# lora-pi-hat.net
KiCad netlist of a schematic drawn in EAGLE
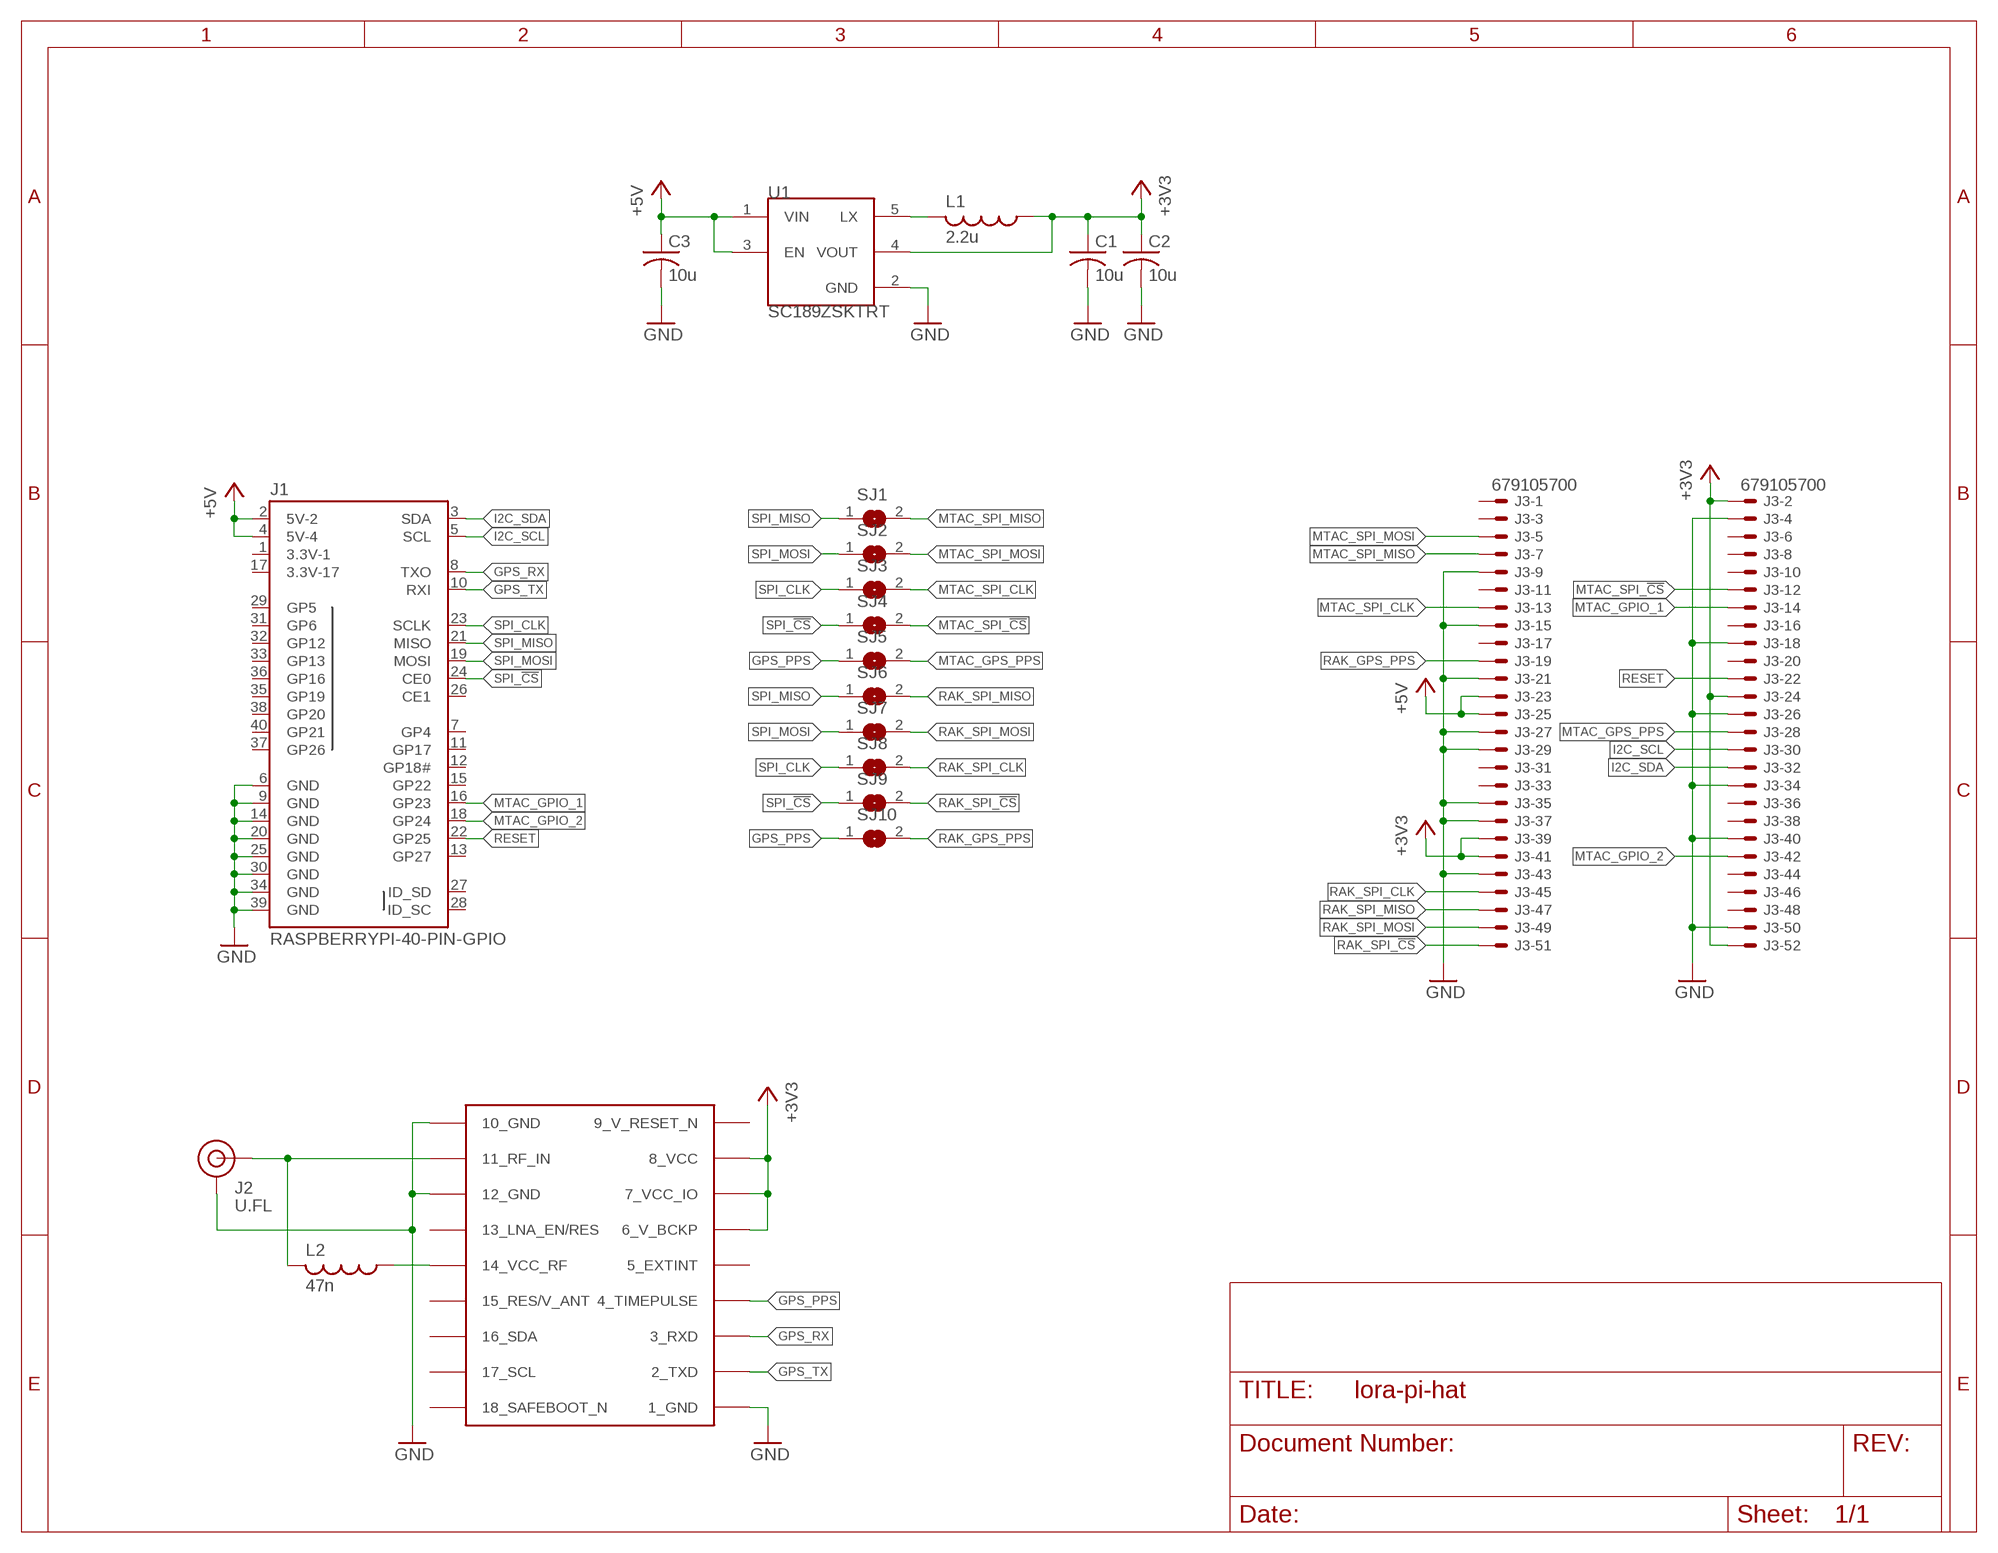
[diagram p0: schematic, sheet 1]

(export (version "E")
  (design (tool "Eeschema 10.0.6"))
  (components
    (comp (ref "C1")
      (value "10u")
      (footprint "eagle-import:CAPC2012X125N")
      (libsource (lib "eagle-import") (part "C-US-0805"))
    )
    (comp (ref "C2")
      (value "10u")
      (footprint "eagle-import:CAPC2012X125N")
      (libsource (lib "eagle-import") (part "C-US-0805"))
    )
    (comp (ref "C3")
      (value "10u")
      (footprint "eagle-import:CAPC2012X125N")
      (libsource (lib "eagle-import") (part "C-US-0805"))
    )
    (comp (ref "J1")
      (value "RASPBERRYPI-40-PIN-GPIO")
      (footprint "eagle-import:2X20")
      (libsource (lib "eagle-import") (part "RASPBERRYPI-40-PIN-GPIO_PTH_NO_SHROUD"))
    )
    (comp (ref "J2")
      (value "U.FL")
      (footprint "eagle-import:U.FL")
      (libsource (lib "eagle-import") (part "U.FL2PIN"))
    )
    (comp (ref "J3")
      (value "679105700")
      (footprint "eagle-import:679105700")
      (fields (field (name "MF") "MOLEX") (field (name "MPN") "67910-5700"))
      (libsource (lib "eagle-import") (part "679105700"))
    )
    (comp (ref "L1")
      (value "2.2u")
      (footprint "eagle-import:INDC3225X250N")
      (libsource (lib "eagle-import") (part "L-US-1210"))
    )
    (comp (ref "L2")
      (value "47n")
      (footprint "eagle-import:INDC2012X125N")
      (libsource (lib "eagle-import") (part "L-US-0805"))
    )
    (comp (ref "SJ1") (value "SJ") (footprint "eagle-import:SJ") (libsource (lib "eagle-import") (part "SJ")))
    (comp (ref "SJ2") (value "SJ") (footprint "eagle-import:SJ") (libsource (lib "eagle-import") (part "SJ")))
    (comp (ref "SJ3") (value "SJ") (footprint "eagle-import:SJ") (libsource (lib "eagle-import") (part "SJ")))
    (comp (ref "SJ4") (value "SJ") (footprint "eagle-import:SJ") (libsource (lib "eagle-import") (part "SJ")))
    (comp (ref "SJ5") (value "SJ") (footprint "eagle-import:SJ") (libsource (lib "eagle-import") (part "SJ")))
    (comp (ref "SJ6") (value "SJ") (footprint "eagle-import:SJ") (libsource (lib "eagle-import") (part "SJ")))
    (comp (ref "SJ7") (value "SJ") (footprint "eagle-import:SJ") (libsource (lib "eagle-import") (part "SJ")))
    (comp (ref "SJ8") (value "SJ") (footprint "eagle-import:SJ") (libsource (lib "eagle-import") (part "SJ")))
    (comp (ref "SJ9") (value "SJ") (footprint "eagle-import:SJ") (libsource (lib "eagle-import") (part "SJ")))
    (comp (ref "SJ10")
      (value "SJ")
      (footprint "eagle-import:SJ")
      (libsource (lib "eagle-import") (part "SJ"))
    )
    (comp (ref "U1")
      (value "SC189ZSKTRT")
      (footprint "eagle-import:SOT95P280X120-5N")
      (libsource (lib "eagle-import") (part "SC189ZSKTRT"))
    )
    (comp (ref "U2")
      (value "MAX-M8")
      (footprint "eagle-import:MAX-M8")
      (libsource (lib "eagle-import") (part "MAX-M8"))
    )
  )
  (nets
    (net (code "1") (name "+3V3") (class "Default")
      (node (ref "C1") (pin "1") (pinfunction "1_1") (pintype "passive"))
      (node (ref "C2") (pin "1") (pinfunction "1_1") (pintype "passive"))
      (node (ref "J3") (pin "2") (pinfunction "S_2") (pintype "passive"))
      (node (ref "J3") (pin "24") (pinfunction "S_24") (pintype "passive"))
      (node (ref "J3") (pin "39") (pinfunction "S_39") (pintype "passive"))
      (node (ref "J3") (pin "41") (pinfunction "S_41") (pintype "passive"))
      (node (ref "J3") (pin "52") (pinfunction "S_52") (pintype "passive"))
      (node (ref "L1") (pin "1") (pinfunction "1_1") (pintype "passive"))
      (node (ref "U1") (pin "4") (pinfunction "VOUT_4") (pintype "bidirectional"))
      (node (ref "U2") (pin "6_V_BCKP") (pinfunction "6_V_BCKP_6_V_BCKP") (pintype "bidirectional"))
      (node (ref "U2") (pin "7_VCC_IO") (pinfunction "7_VCC_IO_7_VCC_IO") (pintype "power_in"))
      (node (ref "U2") (pin "8_VCC") (pinfunction "8_VCC_8_VCC") (pintype "power_in"))
    )
    (net (code "2") (name "+5V") (class "Default")
      (node (ref "C3") (pin "1") (pinfunction "1_1") (pintype "passive"))
      (node (ref "J1") (pin "2") (pinfunction "5V-2_2") (pintype "power_in"))
      (node (ref "J1") (pin "4") (pinfunction "5V-4_4") (pintype "power_in"))
      (node (ref "J3") (pin "23") (pinfunction "S_23") (pintype "passive"))
      (node (ref "J3") (pin "25") (pinfunction "S_25") (pintype "passive"))
      (node (ref "U1") (pin "1") (pinfunction "VIN_1") (pintype "bidirectional"))
      (node (ref "U1") (pin "3") (pinfunction "EN_3") (pintype "bidirectional"))
    )
    (net (code "3") (name "/3.3V-1") (class "Default")
      (node (ref "J1") (pin "1") (pinfunction "3.3V-1_1") (pintype "power_in"))
    )
    (net (code "4") (name "/3.3V-17") (class "Default")
      (node (ref "J1") (pin "17") (pinfunction "3.3V-17_17") (pintype "power_in"))
    )
    (net (code "5") (name "/9_V_RESET_N") (class "Default")
      (node (ref "U2") (pin "9_RESET_N") (pinfunction "9_V_RESET_N_9_RESET_N") (pintype "power_in"))
    )
    (net (code "6") (name "/MTAC_SPI_~{CS}") (class "Default")
      (node (ref "J3") (pin "12") (pinfunction "S_12") (pintype "passive"))
      (node (ref "SJ4") (pin "2") (pinfunction "2_2") (pintype "passive"))
    )
    (net (code "7") (name "/RAK_SPI_~{CS}") (class "Default")
      (node (ref "J3") (pin "51") (pinfunction "S_51") (pintype "passive"))
      (node (ref "SJ9") (pin "2") (pinfunction "2_2") (pintype "passive"))
    )
    (net (code "8") (name "/SPI_~{CS}") (class "Default")
      (node (ref "J1") (pin "24") (pinfunction "CE0_24") (pintype "output"))
      (node (ref "SJ4") (pin "1") (pinfunction "1_1") (pintype "passive"))
      (node (ref "SJ9") (pin "1") (pinfunction "1_1") (pintype "passive"))
    )
    (net (code "9") (name "GND") (class "Default")
      (node (ref "C1") (pin "2") (pinfunction "2_2") (pintype "passive"))
      (node (ref "C2") (pin "2") (pinfunction "2_2") (pintype "passive"))
      (node (ref "C3") (pin "2") (pinfunction "2_2") (pintype "passive"))
      (node (ref "J1") (pin "14") (pinfunction "GND_14") (pintype "power_in"))
      (node (ref "J1") (pin "20") (pinfunction "GND_20") (pintype "power_in"))
      (node (ref "J1") (pin "25") (pinfunction "GND_25") (pintype "power_in"))
      (node (ref "J1") (pin "30") (pinfunction "GND_30") (pintype "power_in"))
      (node (ref "J1") (pin "34") (pinfunction "GND_34") (pintype "power_in"))
      (node (ref "J1") (pin "39") (pinfunction "GND_39") (pintype "power_in"))
      (node (ref "J1") (pin "6") (pinfunction "GND_6") (pintype "power_in"))
      (node (ref "J1") (pin "9") (pinfunction "GND_9") (pintype "power_in"))
      (node (ref "J2") (pin "1") (pinfunction "GND_1") (pintype "bidirectional"))
      (node (ref "J2") (pin "2") (pinfunction "GND_2") (pintype "bidirectional"))
      (node (ref "J3") (pin "15") (pinfunction "S_15") (pintype "passive"))
      (node (ref "J3") (pin "18") (pinfunction "S_18") (pintype "passive"))
      (node (ref "J3") (pin "21") (pinfunction "S_21") (pintype "passive"))
      (node (ref "J3") (pin "26") (pinfunction "S_26") (pintype "passive"))
      (node (ref "J3") (pin "27") (pinfunction "S_27") (pintype "passive"))
      (node (ref "J3") (pin "29") (pinfunction "S_29") (pintype "passive"))
      (node (ref "J3") (pin "34") (pinfunction "S_34") (pintype "passive"))
      (node (ref "J3") (pin "35") (pinfunction "S_35") (pintype "passive"))
      (node (ref "J3") (pin "37") (pinfunction "S_37") (pintype "passive"))
      (node (ref "J3") (pin "4") (pinfunction "S_4") (pintype "passive"))
      (node (ref "J3") (pin "40") (pinfunction "S_40") (pintype "passive"))
      (node (ref "J3") (pin "43") (pinfunction "S_43") (pintype "passive"))
      (node (ref "J3") (pin "50") (pinfunction "S_50") (pintype "passive"))
      (node (ref "J3") (pin "9") (pinfunction "S_9") (pintype "passive"))
      (node (ref "U1") (pin "2") (pinfunction "GND_2") (pintype "bidirectional"))
      (node (ref "U2") (pin "10_GND") (pinfunction "10_GND_10_GND") (pintype "power_in"))
      (node (ref "U2") (pin "12_GND") (pinfunction "12_GND_12_GND") (pintype "power_in"))
      (node (ref "U2") (pin "1_GND") (pinfunction "1_GND_1_GND") (pintype "power_in"))
    )
    (net (code "10") (name "GPS_PPS") (class "Default")
      (node (ref "SJ10") (pin "1") (pinfunction "1_1") (pintype "passive"))
      (node (ref "SJ5") (pin "1") (pinfunction "1_1") (pintype "passive"))
      (node (ref "U2") (pin "4_TIMEPULSE") (pinfunction "4_TIMEPULSE_4_TIMEPULSE") (pintype "bidirectional"))
    )
    (net (code "11") (name "GPS_RX") (class "Default")
      (node (ref "J1") (pin "8") (pinfunction "TXO_8") (pintype "output"))
      (node (ref "U2") (pin "3_RXD") (pinfunction "3_RXD_3_RXD") (pintype "bidirectional"))
    )
    (net (code "12") (name "GPS_TX") (class "Default")
      (node (ref "J1") (pin "10") (pinfunction "RXI_10") (pintype "input"))
      (node (ref "U2") (pin "2_TXD") (pinfunction "2_TXD_2_TXD") (pintype "bidirectional"))
    )
    (net (code "13") (name "I2C_SCL") (class "Default")
      (node (ref "J1") (pin "5") (pinfunction "SCL_5") (pintype "bidirectional"))
      (node (ref "J3") (pin "30") (pinfunction "S_30") (pintype "passive"))
    )
    (net (code "14") (name "I2C_SDA") (class "Default")
      (node (ref "J1") (pin "3") (pinfunction "SDA_3") (pintype "bidirectional"))
      (node (ref "J3") (pin "32") (pinfunction "S_32") (pintype "passive"))
    )
    (net (code "15") (name "MTAC_GPIO_1") (class "Default")
      (node (ref "J1") (pin "16") (pinfunction "GP23_16") (pintype "bidirectional"))
      (node (ref "J3") (pin "14") (pinfunction "S_14") (pintype "passive"))
    )
    (net (code "16") (name "MTAC_GPIO_2") (class "Default")
      (node (ref "J1") (pin "18") (pinfunction "GP24_18") (pintype "bidirectional"))
      (node (ref "J3") (pin "42") (pinfunction "S_42") (pintype "passive"))
    )
    (net (code "17") (name "MTAC_GPS_PPS") (class "Default")
      (node (ref "J3") (pin "28") (pinfunction "S_28") (pintype "passive"))
      (node (ref "SJ5") (pin "2") (pinfunction "2_2") (pintype "passive"))
    )
    (net (code "18") (name "MTAC_SPI_CLK") (class "Default")
      (node (ref "J3") (pin "13") (pinfunction "S_13") (pintype "passive"))
      (node (ref "SJ3") (pin "2") (pinfunction "2_2") (pintype "passive"))
    )
    (net (code "19") (name "MTAC_SPI_MISO") (class "Default")
      (node (ref "J3") (pin "7") (pinfunction "S_7") (pintype "passive"))
      (node (ref "SJ1") (pin "2") (pinfunction "2_2") (pintype "passive"))
    )
    (net (code "20") (name "MTAC_SPI_MOSI") (class "Default")
      (node (ref "J3") (pin "5") (pinfunction "S_5") (pintype "passive"))
      (node (ref "SJ2") (pin "2") (pinfunction "2_2") (pintype "passive"))
    )
    (net (code "21") (name "Net-(J2-SIGNAL)") (class "Default")
      (node (ref "J2") (pin "FEED") (pinfunction "SIGNAL_FEED") (pintype "bidirectional"))
      (node (ref "L2") (pin "2") (pinfunction "2_2") (pintype "passive"))
      (node (ref "U2") (pin "11_RF_IN") (pinfunction "11_RF_IN_11_RF_IN") (pintype "bidirectional"))
    )
    (net (code "22") (name "Net-(L2-Pad1)") (class "Default")
      (node (ref "L2") (pin "1") (pinfunction "1_1") (pintype "passive"))
      (node (ref "U2") (pin "14_VCC_RF") (pinfunction "14_VCC_RF_14_VCC_RF") (pintype "bidirectional"))
    )
    (net (code "23") (name "Net-(U1-LX)") (class "Default")
      (node (ref "L1") (pin "2") (pinfunction "2_2") (pintype "passive"))
      (node (ref "U1") (pin "5") (pinfunction "LX_5") (pintype "bidirectional"))
    )
    (net (code "24") (name "RAK_GPS_PPS") (class "Default")
      (node (ref "J3") (pin "19") (pinfunction "S_19") (pintype "passive"))
      (node (ref "SJ10") (pin "2") (pinfunction "2_2") (pintype "passive"))
    )
    (net (code "25") (name "RAK_SPI_CLK") (class "Default")
      (node (ref "J3") (pin "45") (pinfunction "S_45") (pintype "passive"))
      (node (ref "SJ8") (pin "2") (pinfunction "2_2") (pintype "passive"))
    )
    (net (code "26") (name "RAK_SPI_MISO") (class "Default")
      (node (ref "J3") (pin "47") (pinfunction "S_47") (pintype "passive"))
      (node (ref "SJ6") (pin "2") (pinfunction "2_2") (pintype "passive"))
    )
    (net (code "27") (name "RAK_SPI_MOSI") (class "Default")
      (node (ref "J3") (pin "49") (pinfunction "S_49") (pintype "passive"))
      (node (ref "SJ7") (pin "2") (pinfunction "2_2") (pintype "passive"))
    )
    (net (code "28") (name "RESET") (class "Default")
      (node (ref "J1") (pin "22") (pinfunction "GP25_22") (pintype "bidirectional"))
      (node (ref "J3") (pin "22") (pinfunction "S_22") (pintype "passive"))
    )
    (net (code "29") (name "SPI_CLK") (class "Default")
      (node (ref "J1") (pin "23") (pinfunction "SCLK_23") (pintype "output"))
      (node (ref "SJ3") (pin "1") (pinfunction "1_1") (pintype "passive"))
      (node (ref "SJ8") (pin "1") (pinfunction "1_1") (pintype "passive"))
    )
    (net (code "30") (name "SPI_MISO") (class "Default")
      (node (ref "J1") (pin "21") (pinfunction "MISO_21") (pintype "input"))
      (node (ref "SJ1") (pin "1") (pinfunction "1_1") (pintype "passive"))
      (node (ref "SJ6") (pin "1") (pinfunction "1_1") (pintype "passive"))
    )
    (net (code "31") (name "SPI_MOSI") (class "Default")
      (node (ref "J1") (pin "19") (pinfunction "MOSI_19") (pintype "output"))
      (node (ref "SJ2") (pin "1") (pinfunction "1_1") (pintype "passive"))
      (node (ref "SJ7") (pin "1") (pinfunction "1_1") (pintype "passive"))
    )
    (net (code "32") (name "unconnected-(J1-CE1-Pad26)") (class "Default")
      (node (ref "J1") (pin "26") (pinfunction "CE1_26") (pintype "output"))
    )
    (net (code "33") (name "unconnected-(J1-GP4-Pad7)") (class "Default")
      (node (ref "J1") (pin "7") (pinfunction "GP4_7") (pintype "bidirectional"))
    )
    (net (code "34") (name "unconnected-(J1-GP5-Pad29)") (class "Default")
      (node (ref "J1") (pin "29") (pinfunction "GP5_29") (pintype "bidirectional"))
    )
    (net (code "35") (name "unconnected-(J1-GP6-Pad31)") (class "Default")
      (node (ref "J1") (pin "31") (pinfunction "GP6_31") (pintype "bidirectional"))
    )
    (net (code "36") (name "unconnected-(J1-GP12-Pad32)") (class "Default")
      (node (ref "J1") (pin "32") (pinfunction "GP12_32") (pintype "bidirectional"))
    )
    (net (code "37") (name "unconnected-(J1-GP13-Pad33)") (class "Default")
      (node (ref "J1") (pin "33") (pinfunction "GP13_33") (pintype "bidirectional"))
    )
    (net (code "38") (name "unconnected-(J1-GP16-Pad36)") (class "Default")
      (node (ref "J1") (pin "36") (pinfunction "GP16_36") (pintype "bidirectional"))
    )
    (net (code "39") (name "unconnected-(J1-GP17-Pad11)") (class "Default")
      (node (ref "J1") (pin "11") (pinfunction "GP17_11") (pintype "bidirectional"))
    )
    (net (code "40") (name "unconnected-(J1-GP18#-Pad12)") (class "Default")
      (node (ref "J1") (pin "12") (pinfunction "GP18#_12") (pintype "bidirectional"))
    )
    (net (code "41") (name "unconnected-(J1-GP19-Pad35)") (class "Default")
      (node (ref "J1") (pin "35") (pinfunction "GP19_35") (pintype "bidirectional"))
    )
    (net (code "42") (name "unconnected-(J1-GP20-Pad38)") (class "Default")
      (node (ref "J1") (pin "38") (pinfunction "GP20_38") (pintype "bidirectional"))
    )
    (net (code "43") (name "unconnected-(J1-GP21-Pad40)") (class "Default")
      (node (ref "J1") (pin "40") (pinfunction "GP21_40") (pintype "bidirectional"))
    )
    (net (code "44") (name "unconnected-(J1-GP22-Pad15)") (class "Default")
      (node (ref "J1") (pin "15") (pinfunction "GP22_15") (pintype "bidirectional"))
    )
    (net (code "45") (name "unconnected-(J1-GP26-Pad37)") (class "Default")
      (node (ref "J1") (pin "37") (pinfunction "GP26_37") (pintype "bidirectional"))
    )
    (net (code "46") (name "unconnected-(J1-GP27-Pad13)") (class "Default")
      (node (ref "J1") (pin "13") (pinfunction "GP27_13") (pintype "bidirectional"))
    )
    (net (code "47") (name "unconnected-(J1-ID_SC-Pad28)") (class "Default")
      (node (ref "J1") (pin "28") (pinfunction "ID_SC_28") (pintype "bidirectional"))
    )
    (net (code "48") (name "unconnected-(J1-ID_SD-Pad27)") (class "Default")
      (node (ref "J1") (pin "27") (pinfunction "ID_SD_27") (pintype "bidirectional"))
    )
    (net (code "49") (name "unconnected-(J3A-S-Pad1)") (class "Default")
      (node (ref "J3") (pin "1") (pinfunction "S_1") (pintype "passive"))
    )
    (net (code "50") (name "unconnected-(J3AA-S-Pad33)") (class "Default")
      (node (ref "J3") (pin "33") (pinfunction "S_33") (pintype "passive"))
    )
    (net (code "51") (name "unconnected-(J3AD-S-Pad36)") (class "Default")
      (node (ref "J3") (pin "36") (pinfunction "S_36") (pintype "passive"))
    )
    (net (code "52") (name "unconnected-(J3AF-S-Pad38)") (class "Default")
      (node (ref "J3") (pin "38") (pinfunction "S_38") (pintype "passive"))
    )
    (net (code "53") (name "unconnected-(J3AM-S-Pad44)") (class "Default")
      (node (ref "J3") (pin "44") (pinfunction "S_44") (pintype "passive"))
    )
    (net (code "54") (name "unconnected-(J3AO-S-Pad46)") (class "Default")
      (node (ref "J3") (pin "46") (pinfunction "S_46") (pintype "passive"))
    )
    (net (code "55") (name "unconnected-(J3AQ-S-Pad48)") (class "Default")
      (node (ref "J3") (pin "48") (pinfunction "S_48") (pintype "passive"))
    )
    (net (code "56") (name "unconnected-(J3AW-S-Pad6)") (class "Default")
      (node (ref "J3") (pin "6") (pinfunction "S_6") (pintype "passive"))
    )
    (net (code "57") (name "unconnected-(J3AY-S-Pad8)") (class "Default")
      (node (ref "J3") (pin "8") (pinfunction "S_8") (pintype "passive"))
    )
    (net (code "58") (name "unconnected-(J3B-S-Pad10)") (class "Default")
      (node (ref "J3") (pin "10") (pinfunction "S_10") (pintype "passive"))
    )
    (net (code "59") (name "unconnected-(J3C-S-Pad11)") (class "Default")
      (node (ref "J3") (pin "11") (pinfunction "S_11") (pintype "passive"))
    )
    (net (code "60") (name "unconnected-(J3H-S-Pad16)") (class "Default")
      (node (ref "J3") (pin "16") (pinfunction "S_16") (pintype "passive"))
    )
    (net (code "61") (name "unconnected-(J3I-S-Pad17)") (class "Default")
      (node (ref "J3") (pin "17") (pinfunction "S_17") (pintype "passive"))
    )
    (net (code "62") (name "unconnected-(J3M-S-Pad20)") (class "Default")
      (node (ref "J3") (pin "20") (pinfunction "S_20") (pintype "passive"))
    )
    (net (code "63") (name "unconnected-(J3W-S-Pad3)") (class "Default")
      (node (ref "J3") (pin "3") (pinfunction "S_3") (pintype "passive"))
    )
    (net (code "64") (name "unconnected-(J3Y-S-Pad31)") (class "Default")
      (node (ref "J3") (pin "31") (pinfunction "S_31") (pintype "passive"))
    )
    (net (code "65") (name "unconnected-(U2-13_LNA_EN{slash}RES-Pad13_LNA_EN)") (class "Default")
      (node (ref "U2") (pin "13_LNA_EN") (pinfunction "13_LNA_EN/RES_13_LNA_EN") (pintype "bidirectional"))
    )
    (net (code "66") (name "unconnected-(U2-15_RES{slash}V_ANT-Pad15_V_ANT{slash}RESERVED)") (class "Default")
      (node (ref "U2") (pin "15_V_ANT/RESERVED") (pinfunction "15_RES/V_ANT_15_V_ANT/RESERVED") (pintype "bidirectional"))
    )
    (net (code "67") (name "unconnected-(U2-Pad5_EXTINT)") (class "Default")
      (node (ref "U2") (pin "5_EXTINT") (pinfunction "5_EXTINT_5_EXTINT") (pintype "bidirectional"))
    )
    (net (code "68") (name "unconnected-(U2-Pad16_SDA)") (class "Default")
      (node (ref "U2") (pin "16_SDA") (pinfunction "16_SDA_16_SDA") (pintype "bidirectional"))
    )
    (net (code "69") (name "unconnected-(U2-Pad17_SCL)") (class "Default")
      (node (ref "U2") (pin "17_SCL") (pinfunction "17_SCL_17_SCL") (pintype "bidirectional"))
    )
    (net (code "70") (name "unconnected-(U2-Pad18_SAFEBOOT_N)") (class "Default")
      (node (ref "U2") (pin "18_SAFEBOOT_N") (pinfunction "18_SAFEBOOT_N_18_SAFEBOOT_N") (pintype "bidirectional"))
    )
  )
)
